# dsau-adc-frontend.net
KiCad netlist of a schematic drawn in Altium Designer
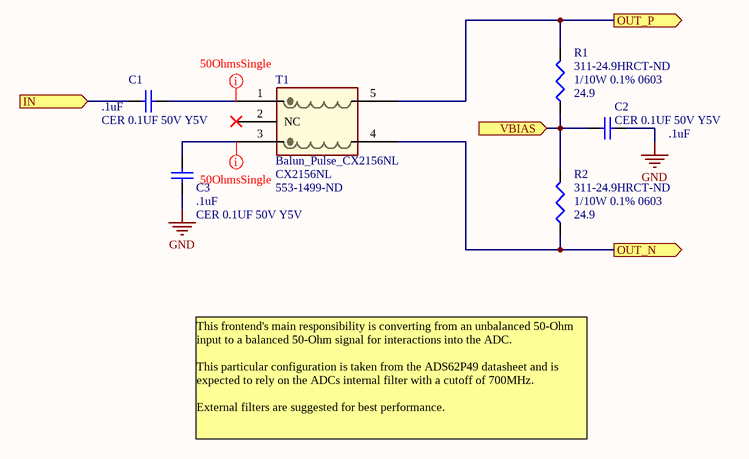
[diagram p0: dsau-adc-frontend.SchDoc]

(export (version "E")
  (design (tool "Eeschema 10.0.6"))
  (components
    (comp (ref "C1")
      (value "CER 0.1UF 50V Y5V")
      (footprint "CAPC1608L")
      (description "Capacitor")
      (fields
        (field (name "ALTIUM_VALUE") ".1uF")
        (field (name "MANUFACTURER") "Yageo")
        (field (name "MANUFACTURER PART NUMBER") "CC0603ZRY5V9BB104")
        (field (name "PUBLISHER") "Altium Limited")
      )
      (libsource (lib "Miscellaneous Devices") (part "Cap"))
    )
    (comp (ref "C2")
      (value "CER 0.1UF 50V Y5V")
      (footprint "CAPC1608L")
      (description "Capacitor")
      (fields
        (field (name "ALTIUM_VALUE") ".1uF")
        (field (name "MANUFACTURER") "Yageo")
        (field (name "MANUFACTURER PART NUMBER") "CC0603ZRY5V9BB104")
        (field (name "PUBLISHER") "Altium Limited")
      )
      (libsource (lib "Miscellaneous Devices") (part "Cap"))
    )
    (comp (ref "C3")
      (value "CER 0.1UF 50V Y5V")
      (footprint "CAPC1608L")
      (description "Capacitor")
      (fields
        (field (name "ALTIUM_VALUE") ".1uF")
        (field (name "MANUFACTURER") "Yageo")
        (field (name "MANUFACTURER PART NUMBER") "CC0603ZRY5V9BB104")
        (field (name "PUBLISHER") "Altium Limited")
      )
      (libsource (lib "Miscellaneous Devices") (part "Cap"))
    )
    (comp (ref "R1")
      (value "1/10W 0.1% 0603")
      (footprint "RESC1608L")
      (description "Resistor")
      (fields
        (field (name "ALTIUM_VALUE") "24.9")
        (field (name "MANUFACTURER") "Yageo")
        (field (name "MANUFACTURER PART NUMBER") "RC0603FR-0724R9L")
        (field (name "SUPPLIER PART NUMBER 1") "311-24.9HRCT-ND")
        (field (name "PUBLISHER") "Altium Limited")
      )
      (libsource (lib "Miscellaneous Devices") (part "Res3"))
    )
    (comp (ref "R2")
      (value "1/10W 0.1% 0603")
      (footprint "RESC1608L")
      (description "Resistor")
      (fields
        (field (name "ALTIUM_VALUE") "24.9")
        (field (name "MANUFACTURER") "Yageo")
        (field (name "MANUFACTURER PART NUMBER") "RC0603FR-0724R9L")
        (field (name "SUPPLIER PART NUMBER 1") "311-24.9HRCT-ND")
        (field (name "PUBLISHER") "Altium Limited")
      )
      (libsource (lib "Miscellaneous Devices") (part "Res3"))
    )
    (comp (ref "T1")
      (value "Balun_Pulse_CX2156NL")
      (footprint "CX2156NL_SMD5")
      (description "TRANSFORMR BALUN 2.3-2700MHZ SMD")
      (fields
        (field (name "MANUFACTURER") "Pulse Electronics Corporation")
        (field (name "MANUFACTURER PART NUMBER") "CX2156NL")
        (field (name "SUPPLIER PART NUMBER 1") "553-1499-ND")
      )
      (libsource (lib "dsau-motherboard") (part "Balun_Pulse_CX2156NL"))
    )
  )
  (nets
    (net (code "1") (name "/IN") (class "Default")
      (node (ref "C1") (pin "1") (pinfunction "1_1") (pintype "passive"))
    )
    (net (code "2") (name "/OUT_N") (class "Default")
      (node (ref "R2") (pin "1") (pinfunction "1_1") (pintype "passive"))
      (node (ref "T1") (pin "4") (pintype "passive"))
    )
    (net (code "3") (name "/OUT_P") (class "Default")
      (node (ref "R1") (pin "2") (pinfunction "2_2") (pintype "passive"))
      (node (ref "T1") (pin "5") (pintype "passive"))
    )
    (net (code "4") (name "/VBIAS") (class "Default")
      (node (ref "C2") (pin "1") (pinfunction "1_1") (pintype "passive"))
      (node (ref "R1") (pin "1") (pinfunction "1_1") (pintype "passive"))
      (node (ref "R2") (pin "2") (pinfunction "2_2") (pintype "passive"))
    )
    (net (code "5") (name "GND") (class "Default")
      (node (ref "C2") (pin "2") (pinfunction "2_2") (pintype "passive"))
      (node (ref "C3") (pin "1") (pinfunction "1_1") (pintype "passive"))
    )
    (net (code "6") (name "Net-(C1-Pad2)") (class "Default")
      (node (ref "C1") (pin "2") (pinfunction "2_2") (pintype "passive"))
      (node (ref "T1") (pin "1") (pintype "passive"))
    )
    (net (code "7") (name "Net-(C3-Pad2)") (class "Default")
      (node (ref "C3") (pin "2") (pinfunction "2_2") (pintype "passive"))
      (node (ref "T1") (pin "3") (pintype "passive"))
    )
    (net (code "8") (name "unconnected-(T1-NC-Pad2)") (class "Default")
      (node (ref "T1") (pin "2") (pinfunction "NC_2") (pintype "passive+no_connect"))
    )
  )
)
